# omnetics-adapter-64.net
KiCad netlist of a schematic drawn in EAGLE
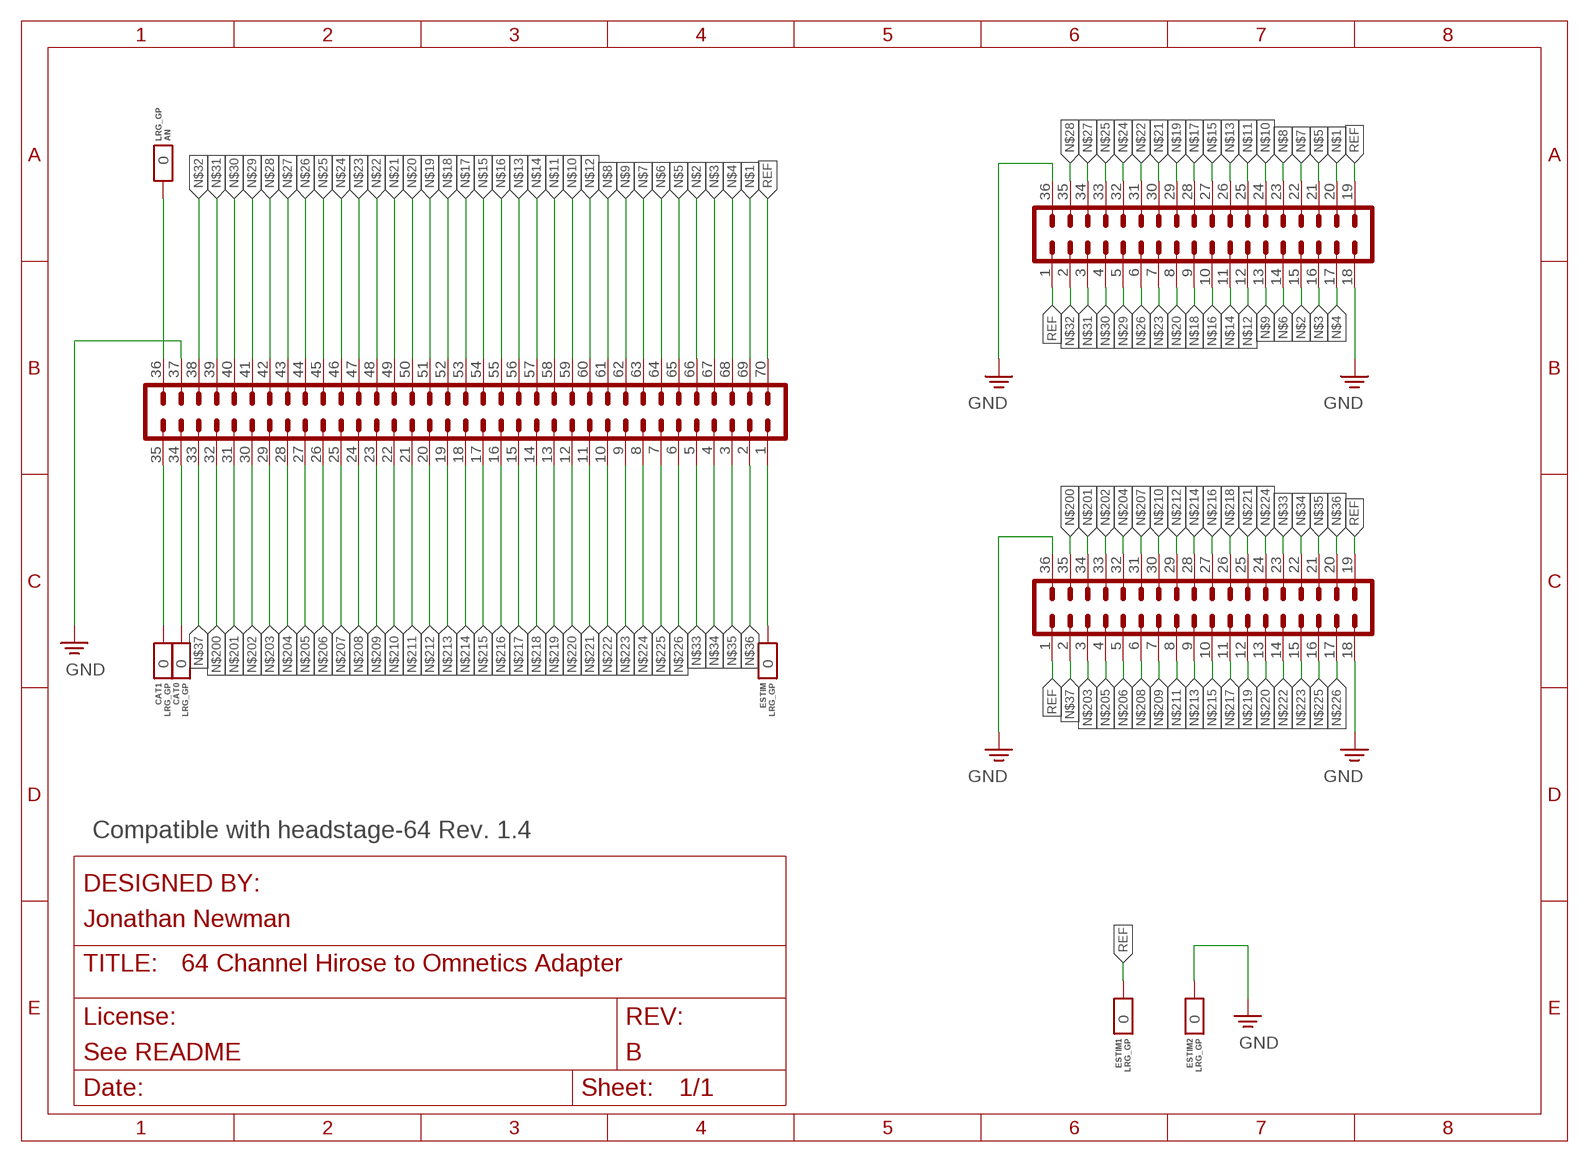
[diagram p0: schematic, sheet 1]

(export (version "E")
  (design (tool "Eeschema 10.0.6"))
  (components
    (comp (ref "AN")
      (value "LRG_GP")
      (footprint "eagle-import:GOLDPIN_0.5ID_0.7OD")
      (libsource (lib "eagle-import") (part "GOLDPIN_0.5ID_0.7OD"))
    )
    (comp (ref "CAT0")
      (value "LRG_GP")
      (footprint "eagle-import:GOLDPIN_0.5ID_0.7OD")
      (libsource (lib "eagle-import") (part "GOLDPIN_0.5ID_0.7OD"))
    )
    (comp (ref "CAT1")
      (value "LRG_GP")
      (footprint "eagle-import:GOLDPIN_0.5ID_0.7OD")
      (libsource (lib "eagle-import") (part "GOLDPIN_0.5ID_0.7OD"))
    )
    (comp (ref "ESTIM")
      (value "LRG_GP")
      (footprint "eagle-import:GOLDPIN_0.5ID_0.7OD")
      (libsource (lib "eagle-import") (part "GOLDPIN_0.5ID_0.7OD"))
    )
    (comp (ref "ESTIM1")
      (value "LRG_GP")
      (footprint "eagle-import:GOLDPIN_0.5ID_0.7OD")
      (libsource (lib "eagle-import") (part "GOLDPIN_0.5ID_0.7OD"))
    )
    (comp (ref "ESTIM2")
      (value "LRG_GP")
      (footprint "eagle-import:GOLDPIN_0.5ID_0.7OD")
      (libsource (lib "eagle-import") (part "GOLDPIN_0.5ID_0.7OD"))
    )
    (comp (ref "J1")
      (value "DF40-REC")
      (footprint "eagle-import:DDF40-70REC-LRG")
      (libsource (lib "eagle-import") (part "PINHD-2X35_DF40REF-LRG"))
    )
    (comp (ref "J2")
      (value "PINHD-2X18_NPD")
      (footprint "eagle-import:NPD-36-VV-GS")
      (libsource (lib "eagle-import") (part "PINHD-2X18_NPD"))
    )
    (comp (ref "J3")
      (value "PINHD-2X18_NPD")
      (footprint "eagle-import:NPD-36-VV-GS")
      (libsource (lib "eagle-import") (part "PINHD-2X18_NPD"))
    )
  )
  (nets
    (net (code "1") (name "GND") (class "Default")
      (node (ref "ESTIM2") (pin "P$1") (pinfunction "0_P$1") (pintype "bidirectional"))
      (node (ref "J1") (pin "37") (pinfunction "37_37") (pintype "bidirectional"))
      (node (ref "J2") (pin "18") (pinfunction "18_18") (pintype "bidirectional"))
      (node (ref "J2") (pin "36") (pinfunction "36_36") (pintype "bidirectional"))
      (node (ref "J3") (pin "18") (pinfunction "18_18") (pintype "bidirectional"))
      (node (ref "J3") (pin "36") (pinfunction "36_36") (pintype "bidirectional"))
    )
    (net (code "2") (name "N$1") (class "Default")
      (node (ref "J1") (pin "69") (pinfunction "69_69") (pintype "bidirectional"))
      (node (ref "J2") (pin "20") (pinfunction "20_20") (pintype "bidirectional"))
    )
    (net (code "3") (name "N$2") (class "Default")
      (node (ref "J1") (pin "66") (pinfunction "66_66") (pintype "bidirectional"))
      (node (ref "J2") (pin "15") (pinfunction "15_15") (pintype "bidirectional"))
    )
    (net (code "4") (name "N$3") (class "Default")
      (node (ref "J1") (pin "67") (pinfunction "67_67") (pintype "bidirectional"))
      (node (ref "J2") (pin "16") (pinfunction "16_16") (pintype "bidirectional"))
    )
    (net (code "5") (name "N$4") (class "Default")
      (node (ref "J1") (pin "68") (pinfunction "68_68") (pintype "bidirectional"))
      (node (ref "J2") (pin "17") (pinfunction "17_17") (pintype "bidirectional"))
    )
    (net (code "6") (name "N$5") (class "Default")
      (node (ref "J1") (pin "65") (pinfunction "65_65") (pintype "bidirectional"))
      (node (ref "J2") (pin "21") (pinfunction "21_21") (pintype "bidirectional"))
    )
    (net (code "7") (name "N$6") (class "Default")
      (node (ref "J1") (pin "64") (pinfunction "64_64") (pintype "bidirectional"))
      (node (ref "J2") (pin "14") (pinfunction "14_14") (pintype "bidirectional"))
    )
    (net (code "8") (name "N$7") (class "Default")
      (node (ref "J1") (pin "63") (pinfunction "63_63") (pintype "bidirectional"))
      (node (ref "J2") (pin "22") (pinfunction "22_22") (pintype "bidirectional"))
    )
    (net (code "9") (name "N$8") (class "Default")
      (node (ref "J1") (pin "61") (pinfunction "61_61") (pintype "bidirectional"))
      (node (ref "J2") (pin "23") (pinfunction "23_23") (pintype "bidirectional"))
    )
    (net (code "10") (name "N$9") (class "Default")
      (node (ref "J1") (pin "62") (pinfunction "62_62") (pintype "bidirectional"))
      (node (ref "J2") (pin "13") (pinfunction "13_13") (pintype "bidirectional"))
    )
    (net (code "11") (name "N$10") (class "Default")
      (node (ref "J1") (pin "59") (pinfunction "59_59") (pintype "bidirectional"))
      (node (ref "J2") (pin "24") (pinfunction "24_24") (pintype "bidirectional"))
    )
    (net (code "12") (name "N$11") (class "Default")
      (node (ref "J1") (pin "58") (pinfunction "58_58") (pintype "bidirectional"))
      (node (ref "J2") (pin "25") (pinfunction "25_25") (pintype "bidirectional"))
    )
    (net (code "13") (name "N$12") (class "Default")
      (node (ref "J1") (pin "60") (pinfunction "60_60") (pintype "bidirectional"))
      (node (ref "J2") (pin "12") (pinfunction "12_12") (pintype "bidirectional"))
    )
    (net (code "14") (name "N$13") (class "Default")
      (node (ref "J1") (pin "56") (pinfunction "56_56") (pintype "bidirectional"))
      (node (ref "J2") (pin "26") (pinfunction "26_26") (pintype "bidirectional"))
    )
    (net (code "15") (name "N$14") (class "Default")
      (node (ref "J1") (pin "57") (pinfunction "57_57") (pintype "bidirectional"))
      (node (ref "J2") (pin "11") (pinfunction "11_11") (pintype "bidirectional"))
    )
    (net (code "16") (name "N$15") (class "Default")
      (node (ref "J1") (pin "54") (pinfunction "54_54") (pintype "bidirectional"))
      (node (ref "J2") (pin "27") (pinfunction "27_27") (pintype "bidirectional"))
    )
    (net (code "17") (name "N$16") (class "Default")
      (node (ref "J1") (pin "55") (pinfunction "55_55") (pintype "bidirectional"))
      (node (ref "J2") (pin "10") (pinfunction "10_10") (pintype "bidirectional"))
    )
    (net (code "18") (name "N$17") (class "Default")
      (node (ref "J1") (pin "53") (pinfunction "53_53") (pintype "bidirectional"))
      (node (ref "J2") (pin "28") (pinfunction "28_28") (pintype "bidirectional"))
    )
    (net (code "19") (name "N$18") (class "Default")
      (node (ref "J1") (pin "52") (pinfunction "52_52") (pintype "bidirectional"))
      (node (ref "J2") (pin "9") (pinfunction "9_9") (pintype "bidirectional"))
    )
    (net (code "20") (name "N$19") (class "Default")
      (node (ref "J1") (pin "51") (pinfunction "51_51") (pintype "bidirectional"))
      (node (ref "J2") (pin "29") (pinfunction "29_29") (pintype "bidirectional"))
    )
    (net (code "21") (name "N$20") (class "Default")
      (node (ref "J1") (pin "50") (pinfunction "50_50") (pintype "bidirectional"))
      (node (ref "J2") (pin "8") (pinfunction "8_8") (pintype "bidirectional"))
    )
    (net (code "22") (name "N$21") (class "Default")
      (node (ref "J1") (pin "49") (pinfunction "49_49") (pintype "bidirectional"))
      (node (ref "J2") (pin "30") (pinfunction "30_30") (pintype "bidirectional"))
    )
    (net (code "23") (name "N$22") (class "Default")
      (node (ref "J1") (pin "48") (pinfunction "48_48") (pintype "bidirectional"))
      (node (ref "J2") (pin "31") (pinfunction "31_31") (pintype "bidirectional"))
    )
    (net (code "24") (name "N$23") (class "Default")
      (node (ref "J1") (pin "47") (pinfunction "47_47") (pintype "bidirectional"))
      (node (ref "J2") (pin "7") (pinfunction "7_7") (pintype "bidirectional"))
    )
    (net (code "25") (name "N$24") (class "Default")
      (node (ref "J1") (pin "46") (pinfunction "46_46") (pintype "bidirectional"))
      (node (ref "J2") (pin "32") (pinfunction "32_32") (pintype "bidirectional"))
    )
    (net (code "26") (name "N$25") (class "Default")
      (node (ref "J1") (pin "45") (pinfunction "45_45") (pintype "bidirectional"))
      (node (ref "J2") (pin "33") (pinfunction "33_33") (pintype "bidirectional"))
    )
    (net (code "27") (name "N$26") (class "Default")
      (node (ref "J1") (pin "44") (pinfunction "44_44") (pintype "bidirectional"))
      (node (ref "J2") (pin "6") (pinfunction "6_6") (pintype "bidirectional"))
    )
    (net (code "28") (name "N$27") (class "Default")
      (node (ref "J1") (pin "43") (pinfunction "43_43") (pintype "bidirectional"))
      (node (ref "J2") (pin "34") (pinfunction "34_34") (pintype "bidirectional"))
    )
    (net (code "29") (name "N$28") (class "Default")
      (node (ref "J1") (pin "42") (pinfunction "42_42") (pintype "bidirectional"))
      (node (ref "J2") (pin "35") (pinfunction "35_35") (pintype "bidirectional"))
    )
    (net (code "30") (name "N$29") (class "Default")
      (node (ref "J1") (pin "41") (pinfunction "41_41") (pintype "bidirectional"))
      (node (ref "J2") (pin "5") (pinfunction "5_5") (pintype "bidirectional"))
    )
    (net (code "31") (name "N$30") (class "Default")
      (node (ref "J1") (pin "40") (pinfunction "40_40") (pintype "bidirectional"))
      (node (ref "J2") (pin "4") (pinfunction "4_4") (pintype "bidirectional"))
    )
    (net (code "32") (name "N$31") (class "Default")
      (node (ref "J1") (pin "39") (pinfunction "39_39") (pintype "bidirectional"))
      (node (ref "J2") (pin "3") (pinfunction "3_3") (pintype "bidirectional"))
    )
    (net (code "33") (name "N$32") (class "Default")
      (node (ref "J1") (pin "38") (pinfunction "38_38") (pintype "bidirectional"))
      (node (ref "J2") (pin "2") (pinfunction "2_2") (pintype "bidirectional"))
    )
    (net (code "34") (name "N$33") (class "Default")
      (node (ref "J1") (pin "5") (pinfunction "5_5") (pintype "bidirectional"))
      (node (ref "J3") (pin "23") (pinfunction "23_23") (pintype "bidirectional"))
    )
    (net (code "35") (name "N$34") (class "Default")
      (node (ref "J1") (pin "4") (pinfunction "4_4") (pintype "bidirectional"))
      (node (ref "J3") (pin "22") (pinfunction "22_22") (pintype "bidirectional"))
    )
    (net (code "36") (name "N$35") (class "Default")
      (node (ref "J1") (pin "3") (pinfunction "3_3") (pintype "bidirectional"))
      (node (ref "J3") (pin "21") (pinfunction "21_21") (pintype "bidirectional"))
    )
    (net (code "37") (name "N$36") (class "Default")
      (node (ref "J1") (pin "2") (pinfunction "2_2") (pintype "bidirectional"))
      (node (ref "J3") (pin "20") (pinfunction "20_20") (pintype "bidirectional"))
    )
    (net (code "38") (name "N$37") (class "Default")
      (node (ref "J1") (pin "33") (pinfunction "33_33") (pintype "bidirectional"))
      (node (ref "J3") (pin "2") (pinfunction "2_2") (pintype "bidirectional"))
    )
    (net (code "39") (name "N$200") (class "Default")
      (node (ref "J1") (pin "32") (pinfunction "32_32") (pintype "bidirectional"))
      (node (ref "J3") (pin "35") (pinfunction "35_35") (pintype "bidirectional"))
    )
    (net (code "40") (name "N$201") (class "Default")
      (node (ref "J1") (pin "31") (pinfunction "31_31") (pintype "bidirectional"))
      (node (ref "J3") (pin "34") (pinfunction "34_34") (pintype "bidirectional"))
    )
    (net (code "41") (name "N$202") (class "Default")
      (node (ref "J1") (pin "30") (pinfunction "30_30") (pintype "bidirectional"))
      (node (ref "J3") (pin "33") (pinfunction "33_33") (pintype "bidirectional"))
    )
    (net (code "42") (name "N$203") (class "Default")
      (node (ref "J1") (pin "29") (pinfunction "29_29") (pintype "bidirectional"))
      (node (ref "J3") (pin "3") (pinfunction "3_3") (pintype "bidirectional"))
    )
    (net (code "43") (name "N$204") (class "Default")
      (node (ref "J1") (pin "28") (pinfunction "28_28") (pintype "bidirectional"))
      (node (ref "J3") (pin "32") (pinfunction "32_32") (pintype "bidirectional"))
    )
    (net (code "44") (name "N$205") (class "Default")
      (node (ref "J1") (pin "27") (pinfunction "27_27") (pintype "bidirectional"))
      (node (ref "J3") (pin "4") (pinfunction "4_4") (pintype "bidirectional"))
    )
    (net (code "45") (name "N$206") (class "Default")
      (node (ref "J1") (pin "26") (pinfunction "26_26") (pintype "bidirectional"))
      (node (ref "J3") (pin "5") (pinfunction "5_5") (pintype "bidirectional"))
    )
    (net (code "46") (name "N$207") (class "Default")
      (node (ref "J1") (pin "25") (pinfunction "25_25") (pintype "bidirectional"))
      (node (ref "J3") (pin "31") (pinfunction "31_31") (pintype "bidirectional"))
    )
    (net (code "47") (name "N$208") (class "Default")
      (node (ref "J1") (pin "24") (pinfunction "24_24") (pintype "bidirectional"))
      (node (ref "J3") (pin "6") (pinfunction "6_6") (pintype "bidirectional"))
    )
    (net (code "48") (name "N$209") (class "Default")
      (node (ref "J1") (pin "23") (pinfunction "23_23") (pintype "bidirectional"))
      (node (ref "J3") (pin "7") (pinfunction "7_7") (pintype "bidirectional"))
    )
    (net (code "49") (name "N$210") (class "Default")
      (node (ref "J1") (pin "22") (pinfunction "22_22") (pintype "bidirectional"))
      (node (ref "J3") (pin "30") (pinfunction "30_30") (pintype "bidirectional"))
    )
    (net (code "50") (name "N$211") (class "Default")
      (node (ref "J1") (pin "21") (pinfunction "21_21") (pintype "bidirectional"))
      (node (ref "J3") (pin "8") (pinfunction "8_8") (pintype "bidirectional"))
    )
    (net (code "51") (name "N$212") (class "Default")
      (node (ref "J1") (pin "20") (pinfunction "20_20") (pintype "bidirectional"))
      (node (ref "J3") (pin "29") (pinfunction "29_29") (pintype "bidirectional"))
    )
    (net (code "52") (name "N$213") (class "Default")
      (node (ref "J1") (pin "19") (pinfunction "19_19") (pintype "bidirectional"))
      (node (ref "J3") (pin "9") (pinfunction "9_9") (pintype "bidirectional"))
    )
    (net (code "53") (name "N$214") (class "Default")
      (node (ref "J1") (pin "18") (pinfunction "18_18") (pintype "bidirectional"))
      (node (ref "J3") (pin "28") (pinfunction "28_28") (pintype "bidirectional"))
    )
    (net (code "54") (name "N$215") (class "Default")
      (node (ref "J1") (pin "17") (pinfunction "17_17") (pintype "bidirectional"))
      (node (ref "J3") (pin "10") (pinfunction "10_10") (pintype "bidirectional"))
    )
    (net (code "55") (name "N$216") (class "Default")
      (node (ref "J1") (pin "16") (pinfunction "16_16") (pintype "bidirectional"))
      (node (ref "J3") (pin "27") (pinfunction "27_27") (pintype "bidirectional"))
    )
    (net (code "56") (name "N$217") (class "Default")
      (node (ref "J1") (pin "15") (pinfunction "15_15") (pintype "bidirectional"))
      (node (ref "J3") (pin "11") (pinfunction "11_11") (pintype "bidirectional"))
    )
    (net (code "57") (name "N$218") (class "Default")
      (node (ref "J1") (pin "14") (pinfunction "14_14") (pintype "bidirectional"))
      (node (ref "J3") (pin "26") (pinfunction "26_26") (pintype "bidirectional"))
    )
    (net (code "58") (name "N$219") (class "Default")
      (node (ref "J1") (pin "13") (pinfunction "13_13") (pintype "bidirectional"))
      (node (ref "J3") (pin "12") (pinfunction "12_12") (pintype "bidirectional"))
    )
    (net (code "59") (name "N$220") (class "Default")
      (node (ref "J1") (pin "12") (pinfunction "12_12") (pintype "bidirectional"))
      (node (ref "J3") (pin "13") (pinfunction "13_13") (pintype "bidirectional"))
    )
    (net (code "60") (name "N$221") (class "Default")
      (node (ref "J1") (pin "11") (pinfunction "11_11") (pintype "bidirectional"))
      (node (ref "J3") (pin "25") (pinfunction "25_25") (pintype "bidirectional"))
    )
    (net (code "61") (name "N$222") (class "Default")
      (node (ref "J1") (pin "10") (pinfunction "10_10") (pintype "bidirectional"))
      (node (ref "J3") (pin "14") (pinfunction "14_14") (pintype "bidirectional"))
    )
    (net (code "62") (name "N$223") (class "Default")
      (node (ref "J1") (pin "9") (pinfunction "9_9") (pintype "bidirectional"))
      (node (ref "J3") (pin "15") (pinfunction "15_15") (pintype "bidirectional"))
    )
    (net (code "63") (name "N$224") (class "Default")
      (node (ref "J1") (pin "8") (pinfunction "8_8") (pintype "bidirectional"))
      (node (ref "J3") (pin "24") (pinfunction "24_24") (pintype "bidirectional"))
    )
    (net (code "64") (name "N$225") (class "Default")
      (node (ref "J1") (pin "7") (pinfunction "7_7") (pintype "bidirectional"))
      (node (ref "J3") (pin "16") (pinfunction "16_16") (pintype "bidirectional"))
    )
    (net (code "65") (name "N$226") (class "Default")
      (node (ref "J1") (pin "6") (pinfunction "6_6") (pintype "bidirectional"))
      (node (ref "J3") (pin "17") (pinfunction "17_17") (pintype "bidirectional"))
    )
    (net (code "66") (name "Net-(AN-0)") (class "Default")
      (node (ref "AN") (pin "P$1") (pinfunction "0_P$1") (pintype "bidirectional"))
      (node (ref "J1") (pin "36") (pinfunction "36_36") (pintype "bidirectional"))
    )
    (net (code "67") (name "Net-(CAT0-0)") (class "Default")
      (node (ref "CAT0") (pin "P$1") (pinfunction "0_P$1") (pintype "bidirectional"))
      (node (ref "J1") (pin "34") (pinfunction "34_34") (pintype "bidirectional"))
    )
    (net (code "68") (name "Net-(CAT1-0)") (class "Default")
      (node (ref "CAT1") (pin "P$1") (pinfunction "0_P$1") (pintype "bidirectional"))
      (node (ref "J1") (pin "35") (pinfunction "35_35") (pintype "bidirectional"))
    )
    (net (code "69") (name "Net-(ESTIM-0)") (class "Default")
      (node (ref "ESTIM") (pin "P$1") (pinfunction "0_P$1") (pintype "bidirectional"))
      (node (ref "J1") (pin "1") (pinfunction "1_1") (pintype "bidirectional"))
    )
    (net (code "70") (name "REF") (class "Default")
      (node (ref "ESTIM1") (pin "P$1") (pinfunction "0_P$1") (pintype "bidirectional"))
      (node (ref "J1") (pin "70") (pinfunction "70_70") (pintype "bidirectional"))
      (node (ref "J2") (pin "1") (pinfunction "1_1") (pintype "bidirectional"))
      (node (ref "J2") (pin "19") (pinfunction "19_19") (pintype "bidirectional"))
      (node (ref "J3") (pin "1") (pinfunction "1_1") (pintype "bidirectional"))
      (node (ref "J3") (pin "19") (pinfunction "19_19") (pintype "bidirectional"))
    )
  )
)
